# usb2can.net
KiCad netlist of a schematic drawn in EAGLE
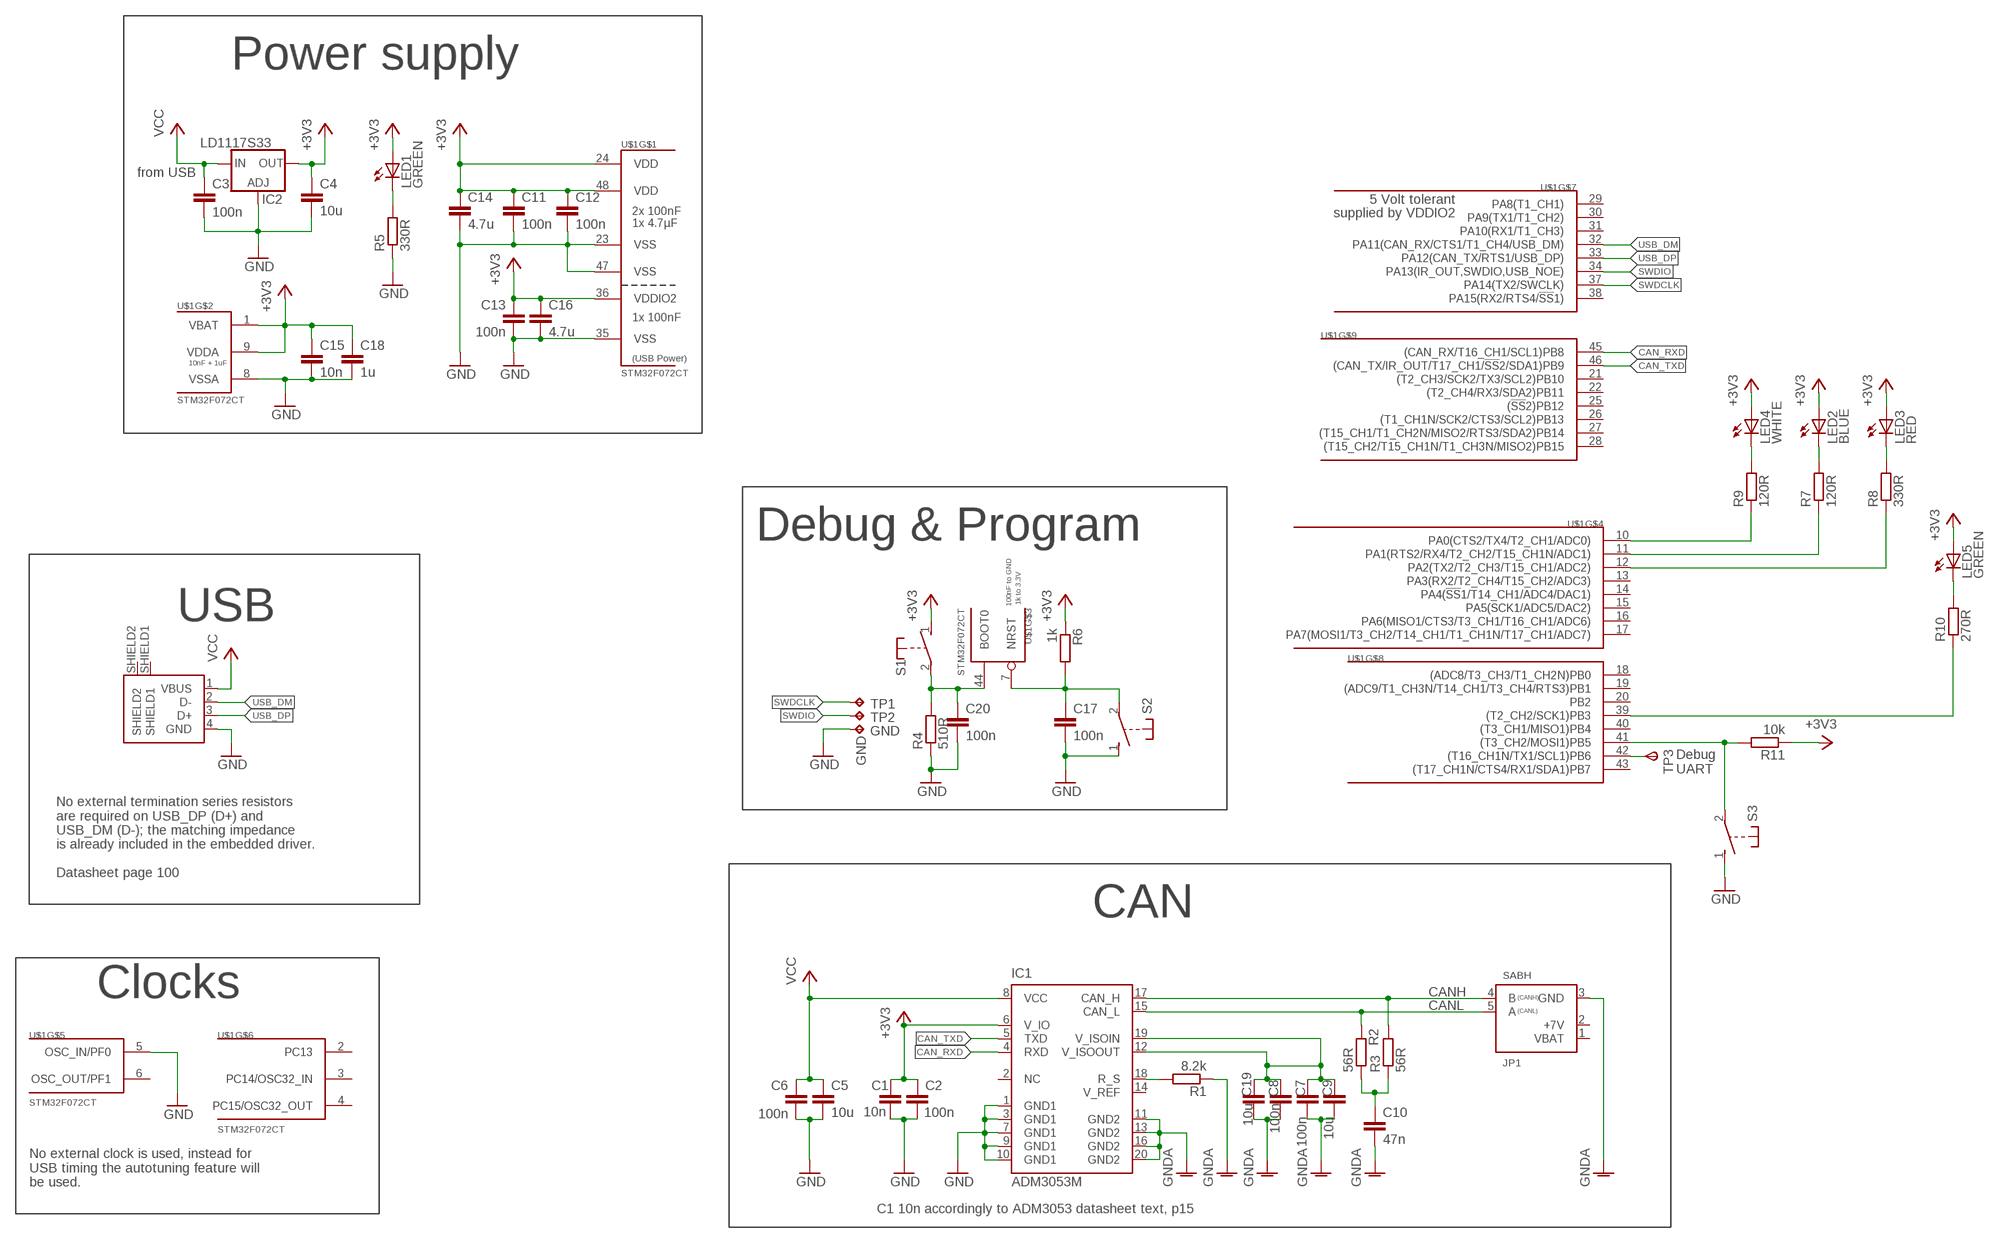
[diagram p0: schematic, sheet 1]

(export (version "E")
  (design (tool "Eeschema 10.0.6"))
  (components
    (comp (ref "C1")
      (value "10n")
      (footprint "eagle-import:C0603K")
      (libsource (lib "eagle-import") (part "C-EUC0603K"))
    )
    (comp (ref "C2")
      (value "100n")
      (footprint "eagle-import:C0603K")
      (libsource (lib "eagle-import") (part "C-EUC0603K"))
    )
    (comp (ref "C3")
      (value "100n")
      (footprint "eagle-import:C0603K")
      (libsource (lib "eagle-import") (part "C-EUC0603K"))
    )
    (comp (ref "C4")
      (value "10u")
      (footprint "eagle-import:C0805K")
      (libsource (lib "eagle-import") (part "C-EUC0805K"))
    )
    (comp (ref "C5")
      (value "10u")
      (footprint "eagle-import:C0805K")
      (libsource (lib "eagle-import") (part "C-EUC0805K"))
    )
    (comp (ref "C6")
      (value "100n")
      (footprint "eagle-import:C0603K")
      (libsource (lib "eagle-import") (part "C-EUC0603K"))
    )
    (comp (ref "C7")
      (value "100n")
      (footprint "eagle-import:C0805K")
      (libsource (lib "eagle-import") (part "C-EUC0805K"))
    )
    (comp (ref "C8")
      (value "100n")
      (footprint "eagle-import:C0805K")
      (libsource (lib "eagle-import") (part "C-EUC0805K"))
    )
    (comp (ref "C9")
      (value "10u")
      (footprint "eagle-import:C0805K")
      (libsource (lib "eagle-import") (part "C-EUC0805K"))
    )
    (comp (ref "C10")
      (value "47n")
      (footprint "eagle-import:C0603K")
      (libsource (lib "eagle-import") (part "C-EUC0603K"))
    )
    (comp (ref "C11")
      (value "100n")
      (footprint "eagle-import:C0603")
      (libsource (lib "eagle-import") (part "C-EUC0603"))
    )
    (comp (ref "C12")
      (value "100n")
      (footprint "eagle-import:C0603")
      (libsource (lib "eagle-import") (part "C-EUC0603"))
    )
    (comp (ref "C13")
      (value "100n")
      (footprint "eagle-import:C0603")
      (libsource (lib "eagle-import") (part "C-EUC0603"))
    )
    (comp (ref "C14")
      (value "4.7u")
      (footprint "eagle-import:C0805K")
      (libsource (lib "eagle-import") (part "C-EUC0805K"))
    )
    (comp (ref "C15")
      (value "10n")
      (footprint "eagle-import:C0603")
      (libsource (lib "eagle-import") (part "C-EUC0603"))
    )
    (comp (ref "C16")
      (value "4.7u")
      (footprint "eagle-import:C0805K")
      (libsource (lib "eagle-import") (part "C-EUC0805K"))
    )
    (comp (ref "C17")
      (value "100n")
      (footprint "eagle-import:C0603")
      (libsource (lib "eagle-import") (part "C-EUC0603"))
    )
    (comp (ref "C18")
      (value "1u")
      (footprint "eagle-import:C0805K")
      (libsource (lib "eagle-import") (part "C-EUC0805K"))
    )
    (comp (ref "C19")
      (value "10u")
      (footprint "eagle-import:C0805K")
      (libsource (lib "eagle-import") (part "C-EUC0805K"))
    )
    (comp (ref "C20")
      (value "100n")
      (footprint "eagle-import:C0603")
      (libsource (lib "eagle-import") (part "C-EUC0603"))
    )
    (comp (ref "CON1")
      (value "USB_A_MALESMD")
      (footprint "eagle-import:USB_A_MALE_SMD")
      (libsource (lib "eagle-import") (part "USB_A_MALESMD"))
    )
    (comp (ref "GND")
      (value "TPB2,54")
      (footprint "eagle-import:B2,54")
      (fields (field (name "TP_SIGNAL_NAME") "GND"))
      (libsource (lib "eagle-import") (part "TPB2,54"))
    )
    (comp (ref "IC1")
      (value "ADM3053M")
      (footprint "eagle-import:SO20W")
      (libsource (lib "eagle-import") (part "ADM3053M"))
    )
    (comp (ref "IC2")
      (value "LD1117S33")
      (footprint "eagle-import:SOT223")
      (libsource (lib "eagle-import") (part "LD117A?S33TR"))
    )
    (comp (ref "JP1")
      (value "SABH")
      (footprint "eagle-import:7395-05")
      (libsource (lib "eagle-import") (part "SABH"))
    )
    (comp (ref "LED1")
      (value "GREEN")
      (footprint "eagle-import:CHIPLED_0603")
      (libsource (lib "eagle-import") (part "LEDCHIPLED_0603"))
    )
    (comp (ref "LED2")
      (value "BLUE")
      (footprint "eagle-import:CHIPLED_0603")
      (libsource (lib "eagle-import") (part "LEDCHIPLED_0603"))
    )
    (comp (ref "LED3")
      (value "RED")
      (footprint "eagle-import:CHIPLED_0603")
      (libsource (lib "eagle-import") (part "LEDCHIPLED_0603"))
    )
    (comp (ref "LED4")
      (value "WHITE")
      (footprint "eagle-import:CHIPLED_0603")
      (libsource (lib "eagle-import") (part "LEDCHIPLED_0603"))
    )
    (comp (ref "LED5")
      (value "GREEN")
      (footprint "eagle-import:CHIPLED_0603")
      (libsource (lib "eagle-import") (part "LEDCHIPLED_0603"))
    )
    (comp (ref "R1")
      (value "8.2k")
      (footprint "eagle-import:R0603")
      (libsource (lib "eagle-import") (part "R-EU_R0603"))
    )
    (comp (ref "R2")
      (value "56R")
      (footprint "eagle-import:R0805")
      (libsource (lib "eagle-import") (part "R-EU_R0805"))
    )
    (comp (ref "R3")
      (value "56R")
      (footprint "eagle-import:R0805")
      (libsource (lib "eagle-import") (part "R-EU_R0805"))
    )
    (comp (ref "R4")
      (value "510R")
      (footprint "eagle-import:R0603")
      (libsource (lib "eagle-import") (part "resistor_R-EU_R0603"))
    )
    (comp (ref "R5")
      (value "330R")
      (footprint "eagle-import:R0603")
      (libsource (lib "eagle-import") (part "resistor_R-EU_R0603"))
    )
    (comp (ref "R6")
      (value "1k")
      (footprint "eagle-import:R0603")
      (libsource (lib "eagle-import") (part "resistor_R-EU_R0603"))
    )
    (comp (ref "R7")
      (value "120R")
      (footprint "eagle-import:R0603")
      (libsource (lib "eagle-import") (part "resistor_R-EU_R0603"))
    )
    (comp (ref "R8")
      (value "330R")
      (footprint "eagle-import:R0603")
      (libsource (lib "eagle-import") (part "resistor_R-EU_R0603"))
    )
    (comp (ref "R9")
      (value "120R")
      (footprint "eagle-import:R0603")
      (libsource (lib "eagle-import") (part "resistor_R-EU_R0603"))
    )
    (comp (ref "R10")
      (value "270R")
      (footprint "eagle-import:R0603")
      (libsource (lib "eagle-import") (part "resistor_R-EU_R0603"))
    )
    (comp (ref "R11")
      (value "10k")
      (footprint "eagle-import:R0603")
      (libsource (lib "eagle-import") (part "resistor_R-EU_R0603"))
    )
    (comp (ref "S1")
      (value "MICRO_SWITCH_3X6X2.5S")
      (footprint "eagle-import:MICRO_SWITCH_3X6X2.5")
      (libsource (lib "eagle-import") (part "MICRO_SWITCH_3X6X2.5S"))
    )
    (comp (ref "S2")
      (value "MICRO_SWITCH_3X6X2.5S")
      (footprint "eagle-import:MICRO_SWITCH_3X6X2.5")
      (libsource (lib "eagle-import") (part "MICRO_SWITCH_3X6X2.5S"))
    )
    (comp (ref "S3")
      (value "MICRO_SWITCH_3X6X2.5S")
      (footprint "eagle-import:MICRO_SWITCH_3X6X2.5")
      (libsource (lib "eagle-import") (part "MICRO_SWITCH_3X6X2.5S"))
    )
    (comp (ref "TP1")
      (value "TPB2,54")
      (footprint "eagle-import:B2,54")
      (libsource (lib "eagle-import") (part "TPB2,54"))
    )
    (comp (ref "TP2")
      (value "TPB2,54")
      (footprint "eagle-import:B2,54")
      (libsource (lib "eagle-import") (part "TPB2,54"))
    )
    (comp (ref "TP3")
      (value "TPSTP07R")
      (footprint "eagle-import:TP07R")
      (libsource (lib "eagle-import") (part "TPSTP07R"))
    )
    (comp (ref "U$1")
      (value "STM32F072CT")
      (footprint "eagle-import:TQFP48")
      (libsource (lib "eagle-import") (part "STM32F072CT"))
    )
  )
  (nets
    (net (code "1") (name "+3V3") (class "Default")
      (node (ref "C1") (pin "1") (pinfunction "1_1") (pintype "passive"))
      (node (ref "C11") (pin "1") (pinfunction "1_1") (pintype "passive"))
      (node (ref "C12") (pin "1") (pinfunction "1_1") (pintype "passive"))
      (node (ref "C13") (pin "1") (pinfunction "1_1") (pintype "passive"))
      (node (ref "C14") (pin "1") (pinfunction "1_1") (pintype "passive"))
      (node (ref "C15") (pin "1") (pinfunction "1_1") (pintype "passive"))
      (node (ref "C16") (pin "1") (pinfunction "1_1") (pintype "passive"))
      (node (ref "C18") (pin "1") (pinfunction "1_1") (pintype "passive"))
      (node (ref "C2") (pin "1") (pinfunction "1_1") (pintype "passive"))
      (node (ref "C4") (pin "1") (pinfunction "1_1") (pintype "passive"))
      (node (ref "IC1") (pin "6") (pinfunction "V_IO_6") (pintype "power_in"))
      (node (ref "IC2") (pin "4") (pinfunction "OUT_4") (pintype "passive"))
      (node (ref "LED1") (pin "A") (pinfunction "A_A") (pintype "passive"))
      (node (ref "LED2") (pin "A") (pinfunction "A_A") (pintype "passive"))
      (node (ref "LED3") (pin "A") (pinfunction "A_A") (pintype "passive"))
      (node (ref "LED4") (pin "A") (pinfunction "A_A") (pintype "passive"))
      (node (ref "LED5") (pin "A") (pinfunction "A_A") (pintype "passive"))
      (node (ref "R11") (pin "1") (pinfunction "1_1") (pintype "passive"))
      (node (ref "R6") (pin "1") (pinfunction "1_1") (pintype "passive"))
      (node (ref "S1") (pin "1") (pinfunction "1_1") (pintype "passive"))
      (node (ref "U$1") (pin "1") (pinfunction "VBAT_1") (pintype "power_in"))
      (node (ref "U$1") (pin "24") (pinfunction "VDD_24") (pintype "power_in"))
      (node (ref "U$1") (pin "36") (pinfunction "VDDIO2_36") (pintype "power_in"))
      (node (ref "U$1") (pin "48") (pinfunction "VDD_48") (pintype "power_in"))
      (node (ref "U$1") (pin "9") (pinfunction "VDDA_9") (pintype "power_in"))
    )
    (net (code "2") (name "/CANH") (class "Default")
      (node (ref "IC1") (pin "17") (pinfunction "CAN_H_17") (pintype "bidirectional"))
      (node (ref "JP1") (pin "4") (pinfunction "B_4") (pintype "bidirectional"))
      (node (ref "R3") (pin "2") (pinfunction "2_2") (pintype "passive"))
    )
    (net (code "3") (name "/CANL") (class "Default")
      (node (ref "IC1") (pin "15") (pinfunction "CAN_L_15") (pintype "bidirectional"))
      (node (ref "JP1") (pin "5") (pinfunction "A_5") (pintype "bidirectional"))
      (node (ref "R2") (pin "2") (pinfunction "2_2") (pintype "passive"))
    )
    (net (code "4") (name "CAN_RXD") (class "Default")
      (node (ref "IC1") (pin "4") (pinfunction "RXD_4") (pintype "output"))
      (node (ref "U$1") (pin "45") (pinfunction "(CAN_RX/T16_CH1/SCL1)PB8_45") (pintype "bidirectional"))
    )
    (net (code "5") (name "CAN_TXD") (class "Default")
      (node (ref "IC1") (pin "5") (pinfunction "TXD_5") (pintype "input"))
      (node (ref "U$1") (pin "46") (pinfunction "(CAN_TX/IR_OUT/T17_CH1/~{SS}2/SDA1)PB9_46") (pintype "bidirectional"))
    )
    (net (code "6") (name "GND") (class "Default")
      (node (ref "C1") (pin "2") (pinfunction "2_2") (pintype "passive"))
      (node (ref "C11") (pin "2") (pinfunction "2_2") (pintype "passive"))
      (node (ref "C12") (pin "2") (pinfunction "2_2") (pintype "passive"))
      (node (ref "C13") (pin "2") (pinfunction "2_2") (pintype "passive"))
      (node (ref "C14") (pin "2") (pinfunction "2_2") (pintype "passive"))
      (node (ref "C15") (pin "2") (pinfunction "2_2") (pintype "passive"))
      (node (ref "C16") (pin "2") (pinfunction "2_2") (pintype "passive"))
      (node (ref "C17") (pin "2") (pinfunction "2_2") (pintype "passive"))
      (node (ref "C18") (pin "2") (pinfunction "2_2") (pintype "passive"))
      (node (ref "C2") (pin "2") (pinfunction "2_2") (pintype "passive"))
      (node (ref "C20") (pin "2") (pinfunction "2_2") (pintype "passive"))
      (node (ref "C3") (pin "2") (pinfunction "2_2") (pintype "passive"))
      (node (ref "C4") (pin "2") (pinfunction "2_2") (pintype "passive"))
      (node (ref "C5") (pin "2") (pinfunction "2_2") (pintype "passive"))
      (node (ref "C6") (pin "2") (pinfunction "2_2") (pintype "passive"))
      (node (ref "CON1") (pin "4") (pinfunction "GND_4") (pintype "power_in"))
      (node (ref "GND") (pin "TP") (pinfunction "TP_TP") (pintype "input"))
      (node (ref "IC1") (pin "1") (pinfunction "GND1_1") (pintype "power_in"))
      (node (ref "IC1") (pin "10") (pinfunction "GND1_10") (pintype "power_in"))
      (node (ref "IC1") (pin "3") (pinfunction "GND1_3") (pintype "power_in"))
      (node (ref "IC1") (pin "7") (pinfunction "GND1_7") (pintype "power_in"))
      (node (ref "IC1") (pin "9") (pinfunction "GND1_9") (pintype "power_in"))
      (node (ref "IC2") (pin "1") (pinfunction "ADJ_1") (pintype "input"))
      (node (ref "R4") (pin "1") (pinfunction "1_1") (pintype "passive"))
      (node (ref "R5") (pin "1") (pinfunction "1_1") (pintype "passive"))
      (node (ref "S2") (pin "1") (pinfunction "1_1") (pintype "passive"))
      (node (ref "S3") (pin "1") (pinfunction "1_1") (pintype "passive"))
      (node (ref "U$1") (pin "23") (pinfunction "VSS_23") (pintype "power_in"))
      (node (ref "U$1") (pin "35") (pinfunction "VSS_35") (pintype "power_in"))
      (node (ref "U$1") (pin "47") (pinfunction "VSS_47") (pintype "power_in"))
      (node (ref "U$1") (pin "5") (pinfunction "OSC_IN/PF0_5") (pintype "input"))
      (node (ref "U$1") (pin "8") (pinfunction "VSSA_8") (pintype "power_in"))
    )
    (net (code "7") (name "GNDA") (class "Default")
      (node (ref "C10") (pin "2") (pinfunction "2_2") (pintype "passive"))
      (node (ref "C19") (pin "2") (pinfunction "2_2") (pintype "passive"))
      (node (ref "C7") (pin "2") (pinfunction "2_2") (pintype "passive"))
      (node (ref "C8") (pin "2") (pinfunction "2_2") (pintype "passive"))
      (node (ref "C9") (pin "2") (pinfunction "2_2") (pintype "passive"))
      (node (ref "IC1") (pin "11") (pinfunction "GND2_11") (pintype "power_in"))
      (node (ref "IC1") (pin "13") (pinfunction "GND2_13") (pintype "power_in"))
      (node (ref "IC1") (pin "16") (pinfunction "GND2_16") (pintype "power_in"))
      (node (ref "IC1") (pin "20") (pinfunction "GND2_20") (pintype "power_in"))
      (node (ref "JP1") (pin "3") (pinfunction "GND_3") (pintype "power_in"))
      (node (ref "R1") (pin "1") (pinfunction "1_1") (pintype "passive"))
    )
    (net (code "8") (name "Net-(C10-Pad1)") (class "Default")
      (node (ref "C10") (pin "1") (pinfunction "1_1") (pintype "passive"))
      (node (ref "R2") (pin "1") (pinfunction "1_1") (pintype "passive"))
      (node (ref "R3") (pin "1") (pinfunction "1_1") (pintype "passive"))
    )
    (net (code "9") (name "Net-(IC1-R_S)") (class "Default")
      (node (ref "IC1") (pin "18") (pinfunction "R_S_18") (pintype "passive"))
      (node (ref "R1") (pin "2") (pinfunction "2_2") (pintype "passive"))
    )
    (net (code "10") (name "Net-(IC1-V_ISOIN)") (class "Default")
      (node (ref "C19") (pin "1") (pinfunction "1_1") (pintype "passive"))
      (node (ref "C7") (pin "1") (pinfunction "1_1") (pintype "passive"))
      (node (ref "C8") (pin "1") (pinfunction "1_1") (pintype "passive"))
      (node (ref "C9") (pin "1") (pinfunction "1_1") (pintype "passive"))
      (node (ref "IC1") (pin "12") (pinfunction "V_ISOOUT_12") (pintype "output"))
      (node (ref "IC1") (pin "19") (pinfunction "V_ISOIN_19") (pintype "input"))
    )
    (net (code "11") (name "Net-(LED1-PadC)") (class "Default")
      (node (ref "LED1") (pin "C") (pinfunction "C_C") (pintype "passive"))
      (node (ref "R5") (pin "2") (pinfunction "2_2") (pintype "passive"))
    )
    (net (code "12") (name "Net-(LED2-PadC)") (class "Default")
      (node (ref "LED2") (pin "C") (pinfunction "C_C") (pintype "passive"))
      (node (ref "R7") (pin "2") (pinfunction "2_2") (pintype "passive"))
    )
    (net (code "13") (name "Net-(LED3-PadC)") (class "Default")
      (node (ref "LED3") (pin "C") (pinfunction "C_C") (pintype "passive"))
      (node (ref "R8") (pin "2") (pinfunction "2_2") (pintype "passive"))
    )
    (net (code "14") (name "Net-(LED4-PadC)") (class "Default")
      (node (ref "LED4") (pin "C") (pinfunction "C_C") (pintype "passive"))
      (node (ref "R9") (pin "2") (pinfunction "2_2") (pintype "passive"))
    )
    (net (code "15") (name "Net-(LED5-PadC)") (class "Default")
      (node (ref "LED5") (pin "C") (pinfunction "C_C") (pintype "passive"))
      (node (ref "R10") (pin "2") (pinfunction "2_2") (pintype "passive"))
    )
    (net (code "16") (name "Net-(TP3-PP)") (class "Default")
      (node (ref "TP3") (pin "TP") (pinfunction "PP_TP") (pintype "input"))
      (node (ref "U$1") (pin "42") (pinfunction "(T16_CH1N/TX1/SCL1)PB6_42") (pintype "bidirectional"))
    )
    (net (code "17") (name "Net-(U$1C-BOOT0)") (class "Default")
      (node (ref "C20") (pin "1") (pinfunction "1_1") (pintype "passive"))
      (node (ref "R4") (pin "2") (pinfunction "2_2") (pintype "passive"))
      (node (ref "S1") (pin "2") (pinfunction "2_2") (pintype "passive"))
      (node (ref "U$1") (pin "44") (pinfunction "BOOT0_44") (pintype "input"))
    )
    (net (code "18") (name "Net-(U$1C-NRST)") (class "Default")
      (node (ref "C17") (pin "1") (pinfunction "1_1") (pintype "passive"))
      (node (ref "R6") (pin "2") (pinfunction "2_2") (pintype "passive"))
      (node (ref "S2") (pin "2") (pinfunction "2_2") (pintype "passive"))
      (node (ref "U$1") (pin "7") (pinfunction "NRST_7") (pintype "input"))
    )
    (net (code "19") (name "Net-(U$1D-PA0(CTS2{slash}TX4{slash}T2_CH1{slash}ADC0))") (class "Default")
      (node (ref "R9") (pin "1") (pinfunction "1_1") (pintype "passive"))
      (node (ref "U$1") (pin "10") (pinfunction "PA0(CTS2/TX4/T2_CH1/ADC0)_10") (pintype "bidirectional"))
    )
    (net (code "20") (name "Net-(U$1D-PA1(RTS2{slash}RX4{slash}T2_CH2{slash}T15_CH1N{slash}ADC1))") (class "Default")
      (node (ref "R7") (pin "1") (pinfunction "1_1") (pintype "passive"))
      (node (ref "U$1") (pin "11") (pinfunction "PA1(RTS2/RX4/T2_CH2/T15_CH1N/ADC1)_11") (pintype "bidirectional"))
    )
    (net (code "21") (name "Net-(U$1D-PA2(TX2{slash}T2_CH3{slash}T15_CH1{slash}ADC2))") (class "Default")
      (node (ref "R8") (pin "1") (pinfunction "1_1") (pintype "passive"))
      (node (ref "U$1") (pin "12") (pinfunction "PA2(TX2/T2_CH3/T15_CH1/ADC2)_12") (pintype "bidirectional"))
    )
    (net (code "22") (name "Net-(U$1H-(T2_CH2{slash}SCK1)PB3)") (class "Default")
      (node (ref "R10") (pin "1") (pinfunction "1_1") (pintype "passive"))
      (node (ref "U$1") (pin "39") (pinfunction "(T2_CH2/SCK1)PB3_39") (pintype "bidirectional"))
    )
    (net (code "23") (name "Net-(U$1H-(T3_CH2{slash}MOSI1)PB5)") (class "Default")
      (node (ref "R11") (pin "2") (pinfunction "2_2") (pintype "passive"))
      (node (ref "S3") (pin "2") (pinfunction "2_2") (pintype "passive"))
      (node (ref "U$1") (pin "41") (pinfunction "(T3_CH2/MOSI1)PB5_41") (pintype "bidirectional"))
    )
    (net (code "24") (name "SWDCLK") (class "Default")
      (node (ref "TP1") (pin "TP") (pinfunction "TP_TP") (pintype "input"))
      (node (ref "U$1") (pin "37") (pinfunction "PA14(TX2/SWCLK)_37") (pintype "bidirectional"))
    )
    (net (code "25") (name "SWDIO") (class "Default")
      (node (ref "TP2") (pin "TP") (pinfunction "TP_TP") (pintype "input"))
      (node (ref "U$1") (pin "34") (pinfunction "PA13(IR_OUT,SWDIO,USB_NOE)_34") (pintype "bidirectional"))
    )
    (net (code "26") (name "USB_DM") (class "Default")
      (node (ref "CON1") (pin "2") (pinfunction "D-_2") (pintype "bidirectional"))
      (node (ref "U$1") (pin "32") (pinfunction "PA11(CAN_RX/CTS1/T1_CH4/USB_DM)_32") (pintype "bidirectional"))
    )
    (net (code "27") (name "USB_DP") (class "Default")
      (node (ref "CON1") (pin "3") (pinfunction "D+_3") (pintype "bidirectional"))
      (node (ref "U$1") (pin "33") (pinfunction "PA12(CAN_TX/RTS1/USB_DP)_33") (pintype "bidirectional"))
    )
    (net (code "28") (name "VCC") (class "Default")
      (node (ref "C3") (pin "1") (pinfunction "1_1") (pintype "passive"))
      (node (ref "C5") (pin "1") (pinfunction "1_1") (pintype "passive"))
      (node (ref "C6") (pin "1") (pinfunction "1_1") (pintype "passive"))
      (node (ref "CON1") (pin "1") (pinfunction "VBUS_1") (pintype "power_in"))
      (node (ref "IC1") (pin "8") (pinfunction "VCC_8") (pintype "power_in"))
      (node (ref "IC2") (pin "3") (pinfunction "IN_3") (pintype "input"))
    )
    (net (code "29") (name "unconnected-(CON1-PadSHIELD1)") (class "Default")
      (node (ref "CON1") (pin "SHIELD1") (pinfunction "SHIELD1_SHIELD1") (pintype "passive"))
    )
    (net (code "30") (name "unconnected-(CON1-PadSHIELD2)") (class "Default")
      (node (ref "CON1") (pin "SHIELD2") (pinfunction "SHIELD2_SHIELD2") (pintype "passive"))
    )
    (net (code "31") (name "unconnected-(IC1-NC-Pad2)") (class "Default")
      (node (ref "IC1") (pin "2") (pinfunction "NC_2") (pintype "no_connect"))
    )
    (net (code "32") (name "unconnected-(IC1-V_REF-Pad14)") (class "Default")
      (node (ref "IC1") (pin "14") (pinfunction "V_REF_14") (pintype "output"))
    )
    (net (code "33") (name "unconnected-(JP1-+7V-Pad2)") (class "Default")
      (node (ref "JP1") (pin "2") (pinfunction "+7V_2") (pintype "no_connect"))
    )
    (net (code "34") (name "unconnected-(JP1-VBAT-Pad1)") (class "Default")
      (node (ref "JP1") (pin "1") (pinfunction "VBAT_1") (pintype "no_connect"))
    )
    (net (code "35") (name "unconnected-(U$1D-PA3(RX2{slash}T2_CH4{slash}T15_CH2{slash}ADC3)-Pad13)") (class "Default")
      (node (ref "U$1") (pin "13") (pinfunction "PA3(RX2/T2_CH4/T15_CH2/ADC3)_13") (pintype "bidirectional"))
    )
    (net (code "36") (name "unconnected-(U$1D-PA4(~{SS}1{slash}T14_CH1{slash}ADC4{slash}DAC1)-Pad14)") (class "Default")
      (node (ref "U$1") (pin "14") (pinfunction "PA4(~{SS}1/T14_CH1/ADC4/DAC1)_14") (pintype "bidirectional"))
    )
    (net (code "37") (name "unconnected-(U$1D-PA5(SCK1{slash}ADC5{slash}DAC2)-Pad15)") (class "Default")
      (node (ref "U$1") (pin "15") (pinfunction "PA5(SCK1/ADC5/DAC2)_15") (pintype "bidirectional"))
    )
    (net (code "38") (name "unconnected-(U$1D-PA6(MISO1{slash}CTS3{slash}T3_CH1{slash}T16_CH1{slash}ADC6)-Pad16)") (class "Default")
      (node (ref "U$1") (pin "16") (pinfunction "PA6(MISO1/CTS3/T3_CH1/T16_CH1/ADC6)_16") (pintype "bidirectional"))
    )
    (net (code "39") (name "unconnected-(U$1D-PA7(MOSI1{slash}T3_CH2{slash}T14_CH1{slash}T1_CH1N{slash}T17_CH1{slash}ADC7)-Pad17)") (class "Default")
      (node (ref "U$1") (pin "17") (pinfunction "PA7(MOSI1/T3_CH2/T14_CH1/T1_CH1N/T17_CH1/ADC7)_17") (pintype "bidirectional"))
    )
    (net (code "40") (name "unconnected-(U$1E-OSC_OUT{slash}PF1-Pad6)") (class "Default")
      (node (ref "U$1") (pin "6") (pinfunction "OSC_OUT/PF1_6") (pintype "output"))
    )
    (net (code "41") (name "unconnected-(U$1F-PC13-Pad2)") (class "Default")
      (node (ref "U$1") (pin "2") (pinfunction "PC13_2") (pintype "bidirectional"))
    )
    (net (code "42") (name "unconnected-(U$1F-PC14{slash}OSC32_IN-Pad3)") (class "Default")
      (node (ref "U$1") (pin "3") (pinfunction "PC14/OSC32_IN_3") (pintype "bidirectional"))
    )
    (net (code "43") (name "unconnected-(U$1F-PC15{slash}OSC32_OUT-Pad4)") (class "Default")
      (node (ref "U$1") (pin "4") (pinfunction "PC15/OSC32_OUT_4") (pintype "bidirectional"))
    )
    (net (code "44") (name "unconnected-(U$1G-PA8(T1_CH1)-Pad29)") (class "Default")
      (node (ref "U$1") (pin "29") (pinfunction "PA8(T1_CH1)_29") (pintype "bidirectional"))
    )
    (net (code "45") (name "unconnected-(U$1G-PA9(TX1{slash}T1_CH2)-Pad30)") (class "Default")
      (node (ref "U$1") (pin "30") (pinfunction "PA9(TX1/T1_CH2)_30") (pintype "bidirectional"))
    )
    (net (code "46") (name "unconnected-(U$1G-PA10(RX1{slash}T1_CH3)-Pad31)") (class "Default")
      (node (ref "U$1") (pin "31") (pinfunction "PA10(RX1/T1_CH3)_31") (pintype "bidirectional"))
    )
    (net (code "47") (name "unconnected-(U$1G-PA15(RX2{slash}RTS4{slash}~{SS}1)-Pad38)") (class "Default")
      (node (ref "U$1") (pin "38") (pinfunction "PA15(RX2/RTS4/~{SS}1)_38") (pintype "bidirectional"))
    )
    (net (code "48") (name "unconnected-(U$1H-(ADC8{slash}T3_CH3{slash}T1_CH2N)PB0-Pad18)") (class "Default")
      (node (ref "U$1") (pin "18") (pinfunction "(ADC8/T3_CH3/T1_CH2N)PB0_18") (pintype "bidirectional"))
    )
    (net (code "49") (name "unconnected-(U$1H-(ADC9{slash}T1_CH3N{slash}T14_CH1{slash}T3_CH4{slash}RTS3)PB1-Pad19)") (class "Default")
      (node (ref "U$1") (pin "19") (pinfunction "(ADC9/T1_CH3N/T14_CH1/T3_CH4/RTS3)PB1_19") (pintype "bidirectional"))
    )
    (net (code "50") (name "unconnected-(U$1H-(T3_CH1{slash}MISO1)PB4-Pad40)") (class "Default")
      (node (ref "U$1") (pin "40") (pinfunction "(T3_CH1/MISO1)PB4_40") (pintype "bidirectional"))
    )
    (net (code "51") (name "unconnected-(U$1H-(T17_CH1N{slash}CTS4{slash}RX1{slash}SDA1)PB7-Pad43)") (class "Default")
      (node (ref "U$1") (pin "43") (pinfunction "(T17_CH1N/CTS4/RX1/SDA1)PB7_43") (pintype "bidirectional"))
    )
    (net (code "52") (name "unconnected-(U$1H-PB2-Pad20)") (class "Default")
      (node (ref "U$1") (pin "20") (pinfunction "PB2_20") (pintype "bidirectional"))
    )
    (net (code "53") (name "unconnected-(U$1I-(T1_CH1N{slash}SCK2{slash}CTS3{slash}SCL2)PB13-Pad26)") (class "Default")
      (node (ref "U$1") (pin "26") (pinfunction "(T1_CH1N/SCK2/CTS3/SCL2)PB13_26") (pintype "bidirectional"))
    )
    (net (code "54") (name "unconnected-(U$1I-(T2_CH3{slash}SCK2{slash}TX3{slash}SCL2)PB10-Pad21)") (class "Default")
      (node (ref "U$1") (pin "21") (pinfunction "(T2_CH3/SCK2/TX3/SCL2)PB10_21") (pintype "bidirectional"))
    )
    (net (code "55") (name "unconnected-(U$1I-(T2_CH4{slash}RX3{slash}SDA2)PB11-Pad22)") (class "Default")
      (node (ref "U$1") (pin "22") (pinfunction "(T2_CH4/RX3/SDA2)PB11_22") (pintype "bidirectional"))
    )
    (net (code "56") (name "unconnected-(U$1I-(T15_CH1{slash}T1_CH2N{slash}MISO2{slash}RTS3{slash}SDA2)PB14-Pad27)") (class "Default")
      (node (ref "U$1") (pin "27") (pinfunction "(T15_CH1/T1_CH2N/MISO2/RTS3/SDA2)PB14_27") (pintype "bidirectional"))
    )
    (net (code "57") (name "unconnected-(U$1I-(T15_CH2{slash}T15_CH1N{slash}T1_CH3N{slash}MISO2)PB15-Pad28)") (class "Default")
      (node (ref "U$1") (pin "28") (pinfunction "(T15_CH2/T15_CH1N/T1_CH3N/MISO2)PB15_28") (pintype "bidirectional"))
    )
    (net (code "58") (name "unconnected-(U$1I-(~{SS}2)PB12-Pad25)") (class "Default")
      (node (ref "U$1") (pin "25") (pinfunction "(~{SS}2)PB12_25") (pintype "bidirectional"))
    )
  )
)
